# Laser_Module_Adapter_PCB.net
KiCad netlist of a schematic drawn in Altium Designer
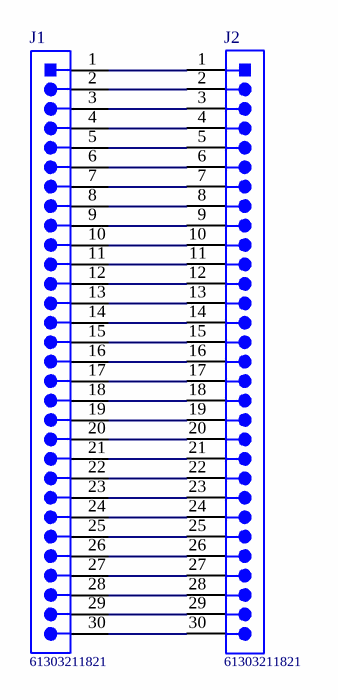
[diagram p0: Laser_Module_Adapter_PCB.SchDoc]

(export (version "E")
  (design (tool "Eeschema 10.0.6"))
  (components
    (comp (ref "J1")
      (value "61303211821")
      (footprint "61303211821_30")
      (description "WR-PHD socket Header, THT, pitch 2.54mm, Single Row, Angled, 32p")
      (fields (field (name "MANUFACTURER") "Wurth Elektronik"))
      (libsource (lib "Connectors") (part "CON_1x30_2.54_61303211821"))
    )
    (comp (ref "J2")
      (value "61303211821")
      (footprint "61303211821_30")
      (description "WR-PHD socket Header, THT, pitch 2.54mm, Single Row, Angled, 32p")
      (fields (field (name "MANUFACTURER") "Wurth Elektronik"))
      (libsource (lib "Connectors") (part "CON_1x30_2.54_61303211821"))
    )
  )
  (nets
    (net (code "1") (name "Net-(J1-Pad1)") (class "Default")
      (node (ref "J1") (pin "1") (pinfunction "1_1") (pintype "passive"))
      (node (ref "J2") (pin "1") (pinfunction "1_1") (pintype "passive"))
    )
    (net (code "2") (name "Net-(J1-Pad2)") (class "Default")
      (node (ref "J1") (pin "2") (pinfunction "2_2") (pintype "passive"))
      (node (ref "J2") (pin "2") (pinfunction "2_2") (pintype "passive"))
    )
    (net (code "3") (name "Net-(J1-Pad3)") (class "Default")
      (node (ref "J1") (pin "3") (pinfunction "3_3") (pintype "passive"))
      (node (ref "J2") (pin "3") (pinfunction "3_3") (pintype "passive"))
    )
    (net (code "4") (name "Net-(J1-Pad4)") (class "Default")
      (node (ref "J1") (pin "4") (pinfunction "4_4") (pintype "passive"))
      (node (ref "J2") (pin "4") (pinfunction "4_4") (pintype "passive"))
    )
    (net (code "5") (name "Net-(J1-Pad5)") (class "Default")
      (node (ref "J1") (pin "5") (pinfunction "5_5") (pintype "passive"))
      (node (ref "J2") (pin "5") (pinfunction "5_5") (pintype "passive"))
    )
    (net (code "6") (name "Net-(J1-Pad6)") (class "Default")
      (node (ref "J1") (pin "6") (pinfunction "6_6") (pintype "passive"))
      (node (ref "J2") (pin "6") (pinfunction "6_6") (pintype "passive"))
    )
    (net (code "7") (name "Net-(J1-Pad7)") (class "Default")
      (node (ref "J1") (pin "7") (pinfunction "7_7") (pintype "passive"))
      (node (ref "J2") (pin "7") (pinfunction "7_7") (pintype "passive"))
    )
    (net (code "8") (name "Net-(J1-Pad8)") (class "Default")
      (node (ref "J1") (pin "8") (pinfunction "8_8") (pintype "passive"))
      (node (ref "J2") (pin "8") (pinfunction "8_8") (pintype "passive"))
    )
    (net (code "9") (name "Net-(J1-Pad9)") (class "Default")
      (node (ref "J1") (pin "9") (pinfunction "9_9") (pintype "passive"))
      (node (ref "J2") (pin "9") (pinfunction "9_9") (pintype "passive"))
    )
    (net (code "10") (name "Net-(J1-Pad10)") (class "Default")
      (node (ref "J1") (pin "10") (pinfunction "10_10") (pintype "passive"))
      (node (ref "J2") (pin "10") (pinfunction "10_10") (pintype "passive"))
    )
    (net (code "11") (name "Net-(J1-Pad11)") (class "Default")
      (node (ref "J1") (pin "11") (pinfunction "11_11") (pintype "passive"))
      (node (ref "J2") (pin "11") (pinfunction "11_11") (pintype "passive"))
    )
    (net (code "12") (name "Net-(J1-Pad12)") (class "Default")
      (node (ref "J1") (pin "12") (pinfunction "12_12") (pintype "passive"))
      (node (ref "J2") (pin "12") (pinfunction "12_12") (pintype "passive"))
    )
    (net (code "13") (name "Net-(J1-Pad13)") (class "Default")
      (node (ref "J1") (pin "13") (pinfunction "13_13") (pintype "passive"))
      (node (ref "J2") (pin "13") (pinfunction "13_13") (pintype "passive"))
    )
    (net (code "14") (name "Net-(J1-Pad14)") (class "Default")
      (node (ref "J1") (pin "14") (pinfunction "14_14") (pintype "passive"))
      (node (ref "J2") (pin "14") (pinfunction "14_14") (pintype "passive"))
    )
    (net (code "15") (name "Net-(J1-Pad15)") (class "Default")
      (node (ref "J1") (pin "15") (pinfunction "15_15") (pintype "passive"))
      (node (ref "J2") (pin "15") (pinfunction "15_15") (pintype "passive"))
    )
    (net (code "16") (name "Net-(J1-Pad16)") (class "Default")
      (node (ref "J1") (pin "16") (pinfunction "16_16") (pintype "passive"))
      (node (ref "J2") (pin "16") (pinfunction "16_16") (pintype "passive"))
    )
    (net (code "17") (name "Net-(J1-Pad17)") (class "Default")
      (node (ref "J1") (pin "17") (pinfunction "17_17") (pintype "passive"))
      (node (ref "J2") (pin "17") (pinfunction "17_17") (pintype "passive"))
    )
    (net (code "18") (name "Net-(J1-Pad18)") (class "Default")
      (node (ref "J1") (pin "18") (pinfunction "18_18") (pintype "passive"))
      (node (ref "J2") (pin "18") (pinfunction "18_18") (pintype "passive"))
    )
    (net (code "19") (name "Net-(J1-Pad19)") (class "Default")
      (node (ref "J1") (pin "19") (pinfunction "19_19") (pintype "passive"))
      (node (ref "J2") (pin "19") (pinfunction "19_19") (pintype "passive"))
    )
    (net (code "20") (name "Net-(J1-Pad20)") (class "Default")
      (node (ref "J1") (pin "20") (pinfunction "20_20") (pintype "passive"))
      (node (ref "J2") (pin "20") (pinfunction "20_20") (pintype "passive"))
    )
    (net (code "21") (name "Net-(J1-Pad21)") (class "Default")
      (node (ref "J1") (pin "21") (pinfunction "21_21") (pintype "passive"))
      (node (ref "J2") (pin "21") (pinfunction "21_21") (pintype "passive"))
    )
    (net (code "22") (name "Net-(J1-Pad22)") (class "Default")
      (node (ref "J1") (pin "22") (pinfunction "22_22") (pintype "passive"))
      (node (ref "J2") (pin "22") (pinfunction "22_22") (pintype "passive"))
    )
    (net (code "23") (name "Net-(J1-Pad23)") (class "Default")
      (node (ref "J1") (pin "23") (pinfunction "23_23") (pintype "passive"))
      (node (ref "J2") (pin "23") (pinfunction "23_23") (pintype "passive"))
    )
    (net (code "24") (name "Net-(J1-Pad24)") (class "Default")
      (node (ref "J1") (pin "24") (pinfunction "24_24") (pintype "passive"))
      (node (ref "J2") (pin "24") (pinfunction "24_24") (pintype "passive"))
    )
    (net (code "25") (name "Net-(J1-Pad25)") (class "Default")
      (node (ref "J1") (pin "25") (pinfunction "25_25") (pintype "passive"))
      (node (ref "J2") (pin "25") (pinfunction "25_25") (pintype "passive"))
    )
    (net (code "26") (name "Net-(J1-Pad26)") (class "Default")
      (node (ref "J1") (pin "26") (pinfunction "26_26") (pintype "passive"))
      (node (ref "J2") (pin "26") (pinfunction "26_26") (pintype "passive"))
    )
    (net (code "27") (name "Net-(J1-Pad27)") (class "Default")
      (node (ref "J1") (pin "27") (pinfunction "27_27") (pintype "passive"))
      (node (ref "J2") (pin "27") (pinfunction "27_27") (pintype "passive"))
    )
    (net (code "28") (name "Net-(J1-Pad28)") (class "Default")
      (node (ref "J1") (pin "28") (pinfunction "28_28") (pintype "passive"))
      (node (ref "J2") (pin "28") (pinfunction "28_28") (pintype "passive"))
    )
    (net (code "29") (name "Net-(J1-Pad29)") (class "Default")
      (node (ref "J1") (pin "29") (pinfunction "29_29") (pintype "passive"))
      (node (ref "J2") (pin "29") (pinfunction "29_29") (pintype "passive"))
    )
    (net (code "30") (name "Net-(J1-Pad30)") (class "Default")
      (node (ref "J1") (pin "30") (pinfunction "30_30") (pintype "passive"))
      (node (ref "J2") (pin "30") (pinfunction "30_30") (pintype "passive"))
    )
  )
)
